# power_supply_board.net
KiCad netlist of a schematic drawn in EAGLE
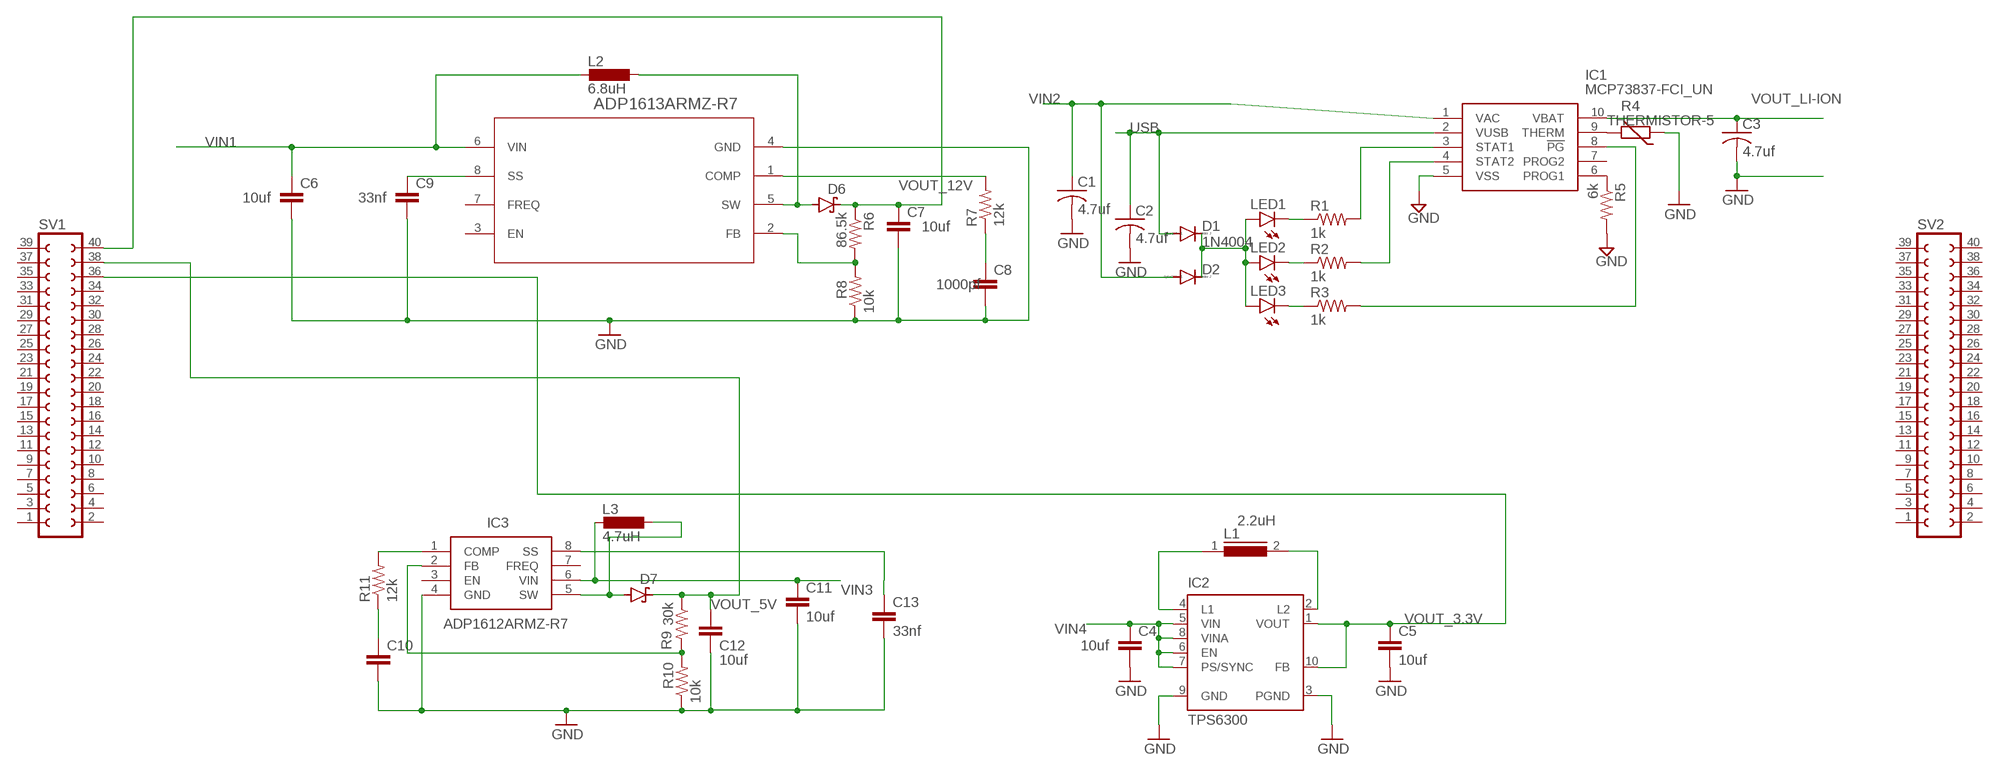
[diagram p0: schematic, sheet 1]

(export (version "E")
  (design (tool "Eeschema 10.0.6"))
  (components
    (comp (ref "C1")
      (value "4.7uf")
      (footprint "eagle-import:C025-024X044")
      (libsource (lib "eagle-import") (part "C-US025-024X044"))
    )
    (comp (ref "C2")
      (value "4.7uf")
      (footprint "eagle-import:C025-024X044")
      (libsource (lib "eagle-import") (part "C-US025-024X044"))
    )
    (comp (ref "C3")
      (value "4.7uf")
      (footprint "eagle-import:C025-024X044")
      (libsource (lib "eagle-import") (part "C-US025-024X044"))
    )
    (comp (ref "C4")
      (value "10uf")
      (footprint "eagle-import:C2.5-3")
      (libsource (lib "eagle-import") (part "C2,5-3"))
    )
    (comp (ref "C5")
      (value "10uf")
      (footprint "eagle-import:C2.5-3")
      (libsource (lib "eagle-import") (part "C2,5-3"))
    )
    (comp (ref "C6")
      (value "10uf")
      (footprint "eagle-import:C2.5-3")
      (libsource (lib "eagle-import") (part "C2,5-3"))
    )
    (comp (ref "C7")
      (value "10uf")
      (footprint "eagle-import:C2.5-3")
      (libsource (lib "eagle-import") (part "C2,5-3"))
    )
    (comp (ref "C8")
      (value "1000pf")
      (footprint "eagle-import:C2.5-3")
      (libsource (lib "eagle-import") (part "C2,5-3"))
    )
    (comp (ref "C9")
      (value "33nf")
      (footprint "eagle-import:C2.5-3")
      (libsource (lib "eagle-import") (part "C2,5-3"))
    )
    (comp (ref "C10")
      (value "1200pf")
      (footprint "eagle-import:C2.5-3")
      (libsource (lib "eagle-import") (part "C2,5-3"))
    )
    (comp (ref "C11")
      (value "10uf")
      (footprint "eagle-import:C2.5-3")
      (libsource (lib "eagle-import") (part "C2,5-3"))
    )
    (comp (ref "C12")
      (value "10uf")
      (footprint "eagle-import:C2.5-3")
      (libsource (lib "eagle-import") (part "C2,5-3"))
    )
    (comp (ref "C13")
      (value "33nf")
      (footprint "eagle-import:C2.5-3")
      (libsource (lib "eagle-import") (part "C2,5-3"))
    )
    (comp (ref "D1")
      (value "1N4004")
      (footprint "eagle-import:DO41-10")
      (libsource (lib "eagle-import") (part "1N4004"))
    )
    (comp (ref "D2")
      (value "1N4004")
      (footprint "eagle-import:DO41-10")
      (libsource (lib "eagle-import") (part "1N4004"))
    )
    (comp (ref "D6")
      (value "3A,40V")
      (footprint "eagle-import:SMC")
      (libsource (lib "eagle-import") (part "MBRS30T32"))
    )
    (comp (ref "D7")
      (value "3A,40V")
      (footprint "eagle-import:SMC")
      (libsource (lib "eagle-import") (part "MBRS30T32"))
    )
    (comp (ref "IC1")
      (value "MCP73837-FCI_UN")
      (footprint "eagle-import:SOP50P490X110-10N")
      (fields
        (field (name "ARROW_PART_NUMBER") "MCP73837-FCI/UN")
        (field (name "MOUSER_PART_NUMBER") "579-MCP73837-FCI/UN")
      )
      (libsource (lib "eagle-import") (part "MCP73837-FCI_UN"))
    )
    (comp (ref "IC2")
      (value "TPS6300")
      (footprint "eagle-import:DRC-S-PVSON-N10")
      (fields (field (name "MPN") "TPS63000DRCTG4"))
      (libsource (lib "eagle-import") (part "TPS6300"))
    )
    (comp (ref "IC3")
      (value "ADP1612ARMZ-R7")
      (footprint "eagle-import:SOP65P490X110-8N")
      (fields (field (name "MOUSER_PART_NUMBER") "584-ADP1612ARMZ-R7"))
      (libsource (lib "eagle-import") (part "ADP1612ARMZ-R7"))
    )
    (comp (ref "L1")
      (value "2.2uH")
      (footprint "eagle-import:SLF7045")
      (libsource (lib "eagle-import") (part "SLF7045"))
    )
    (comp (ref "L2")
      (value "6.8uH")
      (footprint "eagle-import:DO3316P")
      (libsource (lib "eagle-import") (part "DO3316P"))
    )
    (comp (ref "L3")
      (value "4.7uH")
      (footprint "eagle-import:DO3316P")
      (libsource (lib "eagle-import") (part "DO3316P"))
    )
    (comp (ref "LED1")
      (value "LAP4-BOTTOM")
      (footprint "eagle-import:P47F-BOTTOM")
      (libsource (lib "eagle-import") (part "P4-BOTTOMLA"))
    )
    (comp (ref "LED2")
      (value "LAP4-BOTTOM")
      (footprint "eagle-import:P47F-BOTTOM")
      (libsource (lib "eagle-import") (part "P4-BOTTOMLA"))
    )
    (comp (ref "LED3")
      (value "LAP4-BOTTOM")
      (footprint "eagle-import:P47F-BOTTOM")
      (libsource (lib "eagle-import") (part "P4-BOTTOMLA"))
    )
    (comp (ref "R1")
      (value "1k")
      (footprint "eagle-import:0204V")
      (libsource (lib "eagle-import") (part "R-US_0204/2V"))
    )
    (comp (ref "R2")
      (value "1k")
      (footprint "eagle-import:0204V")
      (libsource (lib "eagle-import") (part "R-US_0204/2V"))
    )
    (comp (ref "R3")
      (value "1k")
      (footprint "eagle-import:0204V")
      (libsource (lib "eagle-import") (part "R-US_0204/2V"))
    )
    (comp (ref "R4")
      (value "THERMISTOR-5")
      (footprint "eagle-import:R-5")
      (libsource (lib "eagle-import") (part "THERMISTOR-5"))
    )
    (comp (ref "R5")
      (value "6k")
      (footprint "eagle-import:0204V")
      (libsource (lib "eagle-import") (part "R-US_0204/2V"))
    )
    (comp (ref "R6")
      (value "86.5k")
      (footprint "eagle-import:M0805")
      (libsource (lib "eagle-import") (part "R-US_M0805"))
    )
    (comp (ref "R7")
      (value "12k")
      (footprint "eagle-import:M0805")
      (libsource (lib "eagle-import") (part "R-US_M0805"))
    )
    (comp (ref "R8")
      (value "10k")
      (footprint "eagle-import:M0805")
      (libsource (lib "eagle-import") (part "R-US_M0805"))
    )
    (comp (ref "R9")
      (value "30k")
      (footprint "eagle-import:M0805")
      (libsource (lib "eagle-import") (part "R-US_M0805"))
    )
    (comp (ref "R10")
      (value "10k")
      (footprint "eagle-import:M0805")
      (libsource (lib "eagle-import") (part "R-US_M0805"))
    )
    (comp (ref "R11")
      (value "12k")
      (footprint "eagle-import:M0805")
      (libsource (lib "eagle-import") (part "R-US_M0805"))
    )
    (comp (ref "SV1")
      (value "FE20-2")
      (footprint "eagle-import:FE20-2")
      (libsource (lib "eagle-import") (part "FE20-2"))
    )
    (comp (ref "SV2")
      (value "FE20-2")
      (footprint "eagle-import:FE20-2")
      (libsource (lib "eagle-import") (part "FE20-2"))
    )
    (comp (ref "U1")
      (value "ADP1613ARMZ-R7")
      (footprint "eagle-import:RM_8_ADI")
      (libsource (lib "eagle-import") (part "ADP1613ARMZ-R7"))
    )
  )
  (nets
    (net (code "1") (name "/USB") (class "Default")
      (node (ref "C2") (pin "1") (pinfunction "1_1") (pintype "passive"))
      (node (ref "D1") (pin "A") (pinfunction "A_A") (pintype "passive"))
      (node (ref "IC1") (pin "2") (pinfunction "VUSB_2") (pintype "bidirectional"))
    )
    (net (code "2") (name "/VIN1") (class "Default")
      (node (ref "C6") (pin "1") (pinfunction "1_1") (pintype "passive"))
      (node (ref "L2") (pin "1") (pinfunction "1_1") (pintype "passive"))
      (node (ref "U1") (pin "6") (pinfunction "VIN_6") (pintype "passive"))
    )
    (net (code "3") (name "/VIN2") (class "Default")
      (node (ref "C1") (pin "1") (pinfunction "1_1") (pintype "passive"))
      (node (ref "D2") (pin "A") (pinfunction "A_A") (pintype "passive"))
      (node (ref "IC1") (pin "1") (pinfunction "VAC_1") (pintype "bidirectional"))
    )
    (net (code "4") (name "/VIN3") (class "Default")
      (node (ref "C11") (pin "1") (pinfunction "1_1") (pintype "passive"))
      (node (ref "IC3") (pin "6") (pinfunction "VIN_6") (pintype "bidirectional"))
      (node (ref "L3") (pin "1") (pinfunction "1_1") (pintype "passive"))
    )
    (net (code "5") (name "/VIN4") (class "Default")
      (node (ref "C4") (pin "1") (pinfunction "1_1") (pintype "passive"))
      (node (ref "IC2") (pin "5") (pinfunction "VIN_5") (pintype "input"))
      (node (ref "IC2") (pin "6") (pinfunction "EN_6") (pintype "input"))
      (node (ref "IC2") (pin "7") (pinfunction "PS/SYNC_7") (pintype "input"))
      (node (ref "IC2") (pin "8") (pinfunction "VINA_8") (pintype "input"))
    )
    (net (code "6") (name "/VOUT_3.3V") (class "Default")
      (node (ref "C5") (pin "1") (pinfunction "1_1") (pintype "passive"))
      (node (ref "IC2") (pin "1") (pinfunction "VOUT_1") (pintype "output"))
      (node (ref "IC2") (pin "10") (pinfunction "FB_10") (pintype "input"))
      (node (ref "SV1") (pin "36") (pinfunction "36_36") (pintype "passive"))
    )
    (net (code "7") (name "/VOUT_5V") (class "Default")
      (node (ref "C12") (pin "1") (pinfunction "1_1") (pintype "passive"))
      (node (ref "D7") (pin "C") (pinfunction "C_C") (pintype "passive"))
      (node (ref "R9") (pin "1") (pinfunction "1_1") (pintype "passive"))
      (node (ref "SV1") (pin "38") (pinfunction "38_38") (pintype "passive"))
    )
    (net (code "8") (name "/VOUT_12V") (class "Default")
      (node (ref "C7") (pin "1") (pinfunction "1_1") (pintype "passive"))
      (node (ref "D6") (pin "C") (pinfunction "C_C") (pintype "passive"))
      (node (ref "R6") (pin "1") (pinfunction "1_1") (pintype "passive"))
      (node (ref "SV1") (pin "40") (pinfunction "40_40") (pintype "passive"))
    )
    (net (code "9") (name "/VOUT_LI-ION") (class "Default")
      (node (ref "C3") (pin "1") (pinfunction "1_1") (pintype "passive"))
      (node (ref "IC1") (pin "10") (pinfunction "VBAT_10") (pintype "bidirectional"))
    )
    (net (code "10") (name "GND") (class "Default")
      (node (ref "C1") (pin "2") (pinfunction "2_2") (pintype "passive"))
      (node (ref "C10") (pin "2") (pinfunction "2_2") (pintype "passive"))
      (node (ref "C11") (pin "2") (pinfunction "2_2") (pintype "passive"))
      (node (ref "C12") (pin "2") (pinfunction "2_2") (pintype "passive"))
      (node (ref "C13") (pin "2") (pinfunction "2_2") (pintype "passive"))
      (node (ref "C2") (pin "2") (pinfunction "2_2") (pintype "passive"))
      (node (ref "C3") (pin "2") (pinfunction "2_2") (pintype "passive"))
      (node (ref "C4") (pin "2") (pinfunction "2_2") (pintype "passive"))
      (node (ref "C5") (pin "2") (pinfunction "2_2") (pintype "passive"))
      (node (ref "C6") (pin "2") (pinfunction "2_2") (pintype "passive"))
      (node (ref "C7") (pin "2") (pinfunction "2_2") (pintype "passive"))
      (node (ref "C8") (pin "2") (pinfunction "2_2") (pintype "passive"))
      (node (ref "C9") (pin "2") (pinfunction "2_2") (pintype "passive"))
      (node (ref "IC1") (pin "5") (pinfunction "VSS_5") (pintype "power_in"))
      (node (ref "IC2") (pin "3") (pinfunction "PGND_3") (pintype "power_in"))
      (node (ref "IC2") (pin "9") (pinfunction "GND_9") (pintype "power_in"))
      (node (ref "IC3") (pin "4") (pinfunction "GND_4") (pintype "bidirectional"))
      (node (ref "R10") (pin "1") (pinfunction "1_1") (pintype "passive"))
      (node (ref "R4") (pin "1") (pinfunction "1_1") (pintype "passive"))
      (node (ref "R5") (pin "2") (pinfunction "2_2") (pintype "passive"))
      (node (ref "R8") (pin "1") (pinfunction "1_1") (pintype "passive"))
      (node (ref "U1") (pin "4") (pinfunction "GND_4") (pintype "passive"))
    )
    (net (code "11") (name "Net-(C8-Pad1)") (class "Default")
      (node (ref "C8") (pin "1") (pinfunction "1_1") (pintype "passive"))
      (node (ref "R7") (pin "1") (pinfunction "1_1") (pintype "passive"))
    )
    (net (code "12") (name "Net-(C10-Pad1)") (class "Default")
      (node (ref "C10") (pin "1") (pinfunction "1_1") (pintype "passive"))
      (node (ref "R11") (pin "1") (pinfunction "1_1") (pintype "passive"))
    )
    (net (code "13") (name "Net-(D1-PadC)") (class "Default")
      (node (ref "D1") (pin "C") (pinfunction "C_C") (pintype "passive"))
      (node (ref "D2") (pin "C") (pinfunction "C_C") (pintype "passive"))
      (node (ref "LED1") (pin "A") (pinfunction "A_A") (pintype "passive"))
      (node (ref "LED2") (pin "A") (pinfunction "A_A") (pintype "passive"))
      (node (ref "LED3") (pin "A") (pinfunction "A_A") (pintype "passive"))
    )
    (net (code "14") (name "Net-(IC1-PROG1)") (class "Default")
      (node (ref "IC1") (pin "6") (pinfunction "PROG1_6") (pintype "bidirectional"))
      (node (ref "R5") (pin "1") (pinfunction "1_1") (pintype "passive"))
    )
    (net (code "15") (name "Net-(IC1-STAT1)") (class "Default")
      (node (ref "IC1") (pin "3") (pinfunction "STAT1_3") (pintype "bidirectional"))
      (node (ref "R1") (pin "2") (pinfunction "2_2") (pintype "passive"))
    )
    (net (code "16") (name "Net-(IC1-STAT2)") (class "Default")
      (node (ref "IC1") (pin "4") (pinfunction "STAT2_4") (pintype "bidirectional"))
      (node (ref "R2") (pin "2") (pinfunction "2_2") (pintype "passive"))
    )
    (net (code "17") (name "Net-(IC1-THERM)") (class "Default")
      (node (ref "IC1") (pin "9") (pinfunction "THERM_9") (pintype "bidirectional"))
      (node (ref "R4") (pin "2") (pinfunction "2_2") (pintype "passive"))
    )
    (net (code "18") (name "Net-(IC1-~{PG})") (class "Default")
      (node (ref "IC1") (pin "8") (pinfunction "~{PG}_8") (pintype "bidirectional"))
      (node (ref "R3") (pin "2") (pinfunction "2_2") (pintype "passive"))
    )
    (net (code "19") (name "Net-(IC2A-L1)") (class "Default")
      (node (ref "IC2") (pin "4") (pinfunction "L1_4") (pintype "passive"))
      (node (ref "L1") (pin "1") (pinfunction "1_1") (pintype "passive"))
    )
    (net (code "20") (name "Net-(IC2A-L2)") (class "Default")
      (node (ref "IC2") (pin "2") (pinfunction "L2_2") (pintype "passive"))
      (node (ref "L1") (pin "2") (pinfunction "2_2") (pintype "passive"))
    )
    (net (code "21") (name "Net-(IC3-COMP)") (class "Default")
      (node (ref "IC3") (pin "1") (pinfunction "COMP_1") (pintype "bidirectional"))
      (node (ref "R11") (pin "2") (pinfunction "2_2") (pintype "passive"))
    )
    (net (code "22") (name "Net-(IC3-FB)") (class "Default")
      (node (ref "IC3") (pin "2") (pinfunction "FB_2") (pintype "bidirectional"))
      (node (ref "R10") (pin "2") (pinfunction "2_2") (pintype "passive"))
      (node (ref "R9") (pin "2") (pinfunction "2_2") (pintype "passive"))
    )
    (net (code "23") (name "Net-(IC3-SS)") (class "Default")
      (node (ref "C13") (pin "1") (pinfunction "1_1") (pintype "passive"))
      (node (ref "IC3") (pin "8") (pinfunction "SS_8") (pintype "bidirectional"))
    )
    (net (code "24") (name "Net-(IC3-SW)") (class "Default")
      (node (ref "D7") (pin "A") (pinfunction "A_A") (pintype "passive"))
      (node (ref "IC3") (pin "5") (pinfunction "SW_5") (pintype "bidirectional"))
      (node (ref "L3") (pin "2") (pinfunction "2_2") (pintype "passive"))
    )
    (net (code "25") (name "Net-(LED1-PadC)") (class "Default")
      (node (ref "LED1") (pin "C") (pinfunction "C_C") (pintype "passive"))
      (node (ref "R1") (pin "1") (pinfunction "1_1") (pintype "passive"))
    )
    (net (code "26") (name "Net-(LED2-PadC)") (class "Default")
      (node (ref "LED2") (pin "C") (pinfunction "C_C") (pintype "passive"))
      (node (ref "R2") (pin "1") (pinfunction "1_1") (pintype "passive"))
    )
    (net (code "27") (name "Net-(LED3-PadC)") (class "Default")
      (node (ref "LED3") (pin "C") (pinfunction "C_C") (pintype "passive"))
      (node (ref "R3") (pin "1") (pinfunction "1_1") (pintype "passive"))
    )
    (net (code "28") (name "Net-(U1-COMP)") (class "Default")
      (node (ref "R7") (pin "2") (pinfunction "2_2") (pintype "passive"))
      (node (ref "U1") (pin "1") (pinfunction "COMP_1") (pintype "passive"))
    )
    (net (code "29") (name "Net-(U1-FB)") (class "Default")
      (node (ref "R6") (pin "2") (pinfunction "2_2") (pintype "passive"))
      (node (ref "R8") (pin "2") (pinfunction "2_2") (pintype "passive"))
      (node (ref "U1") (pin "2") (pinfunction "FB_2") (pintype "passive"))
    )
    (net (code "30") (name "Net-(U1-SS)") (class "Default")
      (node (ref "C9") (pin "1") (pinfunction "1_1") (pintype "passive"))
      (node (ref "U1") (pin "8") (pinfunction "SS_8") (pintype "passive"))
    )
    (net (code "31") (name "Net-(U1-SW)") (class "Default")
      (node (ref "D6") (pin "A") (pinfunction "A_A") (pintype "passive"))
      (node (ref "L2") (pin "2") (pinfunction "2_2") (pintype "passive"))
      (node (ref "U1") (pin "5") (pinfunction "SW_5") (pintype "passive"))
    )
    (net (code "32") (name "unconnected-(IC1-PROG2-Pad7)") (class "Default")
      (node (ref "IC1") (pin "7") (pinfunction "PROG2_7") (pintype "bidirectional"))
    )
    (net (code "33") (name "unconnected-(IC3-EN-Pad3)") (class "Default")
      (node (ref "IC3") (pin "3") (pinfunction "EN_3") (pintype "bidirectional"))
    )
    (net (code "34") (name "unconnected-(IC3-FREQ-Pad7)") (class "Default")
      (node (ref "IC3") (pin "7") (pinfunction "FREQ_7") (pintype "bidirectional"))
    )
    (net (code "35") (name "unconnected-(SV1-Pad1)") (class "Default")
      (node (ref "SV1") (pin "1") (pinfunction "1_1") (pintype "passive"))
    )
    (net (code "36") (name "unconnected-(SV1-Pad2)") (class "Default")
      (node (ref "SV1") (pin "2") (pinfunction "2_2") (pintype "passive"))
    )
    (net (code "37") (name "unconnected-(SV1-Pad3)") (class "Default")
      (node (ref "SV1") (pin "3") (pinfunction "3_3") (pintype "passive"))
    )
    (net (code "38") (name "unconnected-(SV1-Pad4)") (class "Default")
      (node (ref "SV1") (pin "4") (pinfunction "4_4") (pintype "passive"))
    )
    (net (code "39") (name "unconnected-(SV1-Pad5)") (class "Default")
      (node (ref "SV1") (pin "5") (pinfunction "5_5") (pintype "passive"))
    )
    (net (code "40") (name "unconnected-(SV1-Pad6)") (class "Default")
      (node (ref "SV1") (pin "6") (pinfunction "6_6") (pintype "passive"))
    )
    (net (code "41") (name "unconnected-(SV1-Pad7)") (class "Default")
      (node (ref "SV1") (pin "7") (pinfunction "7_7") (pintype "passive"))
    )
    (net (code "42") (name "unconnected-(SV1-Pad8)") (class "Default")
      (node (ref "SV1") (pin "8") (pinfunction "8_8") (pintype "passive"))
    )
    (net (code "43") (name "unconnected-(SV1-Pad9)") (class "Default")
      (node (ref "SV1") (pin "9") (pinfunction "9_9") (pintype "passive"))
    )
    (net (code "44") (name "unconnected-(SV1-Pad10)") (class "Default")
      (node (ref "SV1") (pin "10") (pinfunction "10_10") (pintype "passive"))
    )
    (net (code "45") (name "unconnected-(SV1-Pad11)") (class "Default")
      (node (ref "SV1") (pin "11") (pinfunction "11_11") (pintype "passive"))
    )
    (net (code "46") (name "unconnected-(SV1-Pad12)") (class "Default")
      (node (ref "SV1") (pin "12") (pinfunction "12_12") (pintype "passive"))
    )
    (net (code "47") (name "unconnected-(SV1-Pad13)") (class "Default")
      (node (ref "SV1") (pin "13") (pinfunction "13_13") (pintype "passive"))
    )
    (net (code "48") (name "unconnected-(SV1-Pad14)") (class "Default")
      (node (ref "SV1") (pin "14") (pinfunction "14_14") (pintype "passive"))
    )
    (net (code "49") (name "unconnected-(SV1-Pad15)") (class "Default")
      (node (ref "SV1") (pin "15") (pinfunction "15_15") (pintype "passive"))
    )
    (net (code "50") (name "unconnected-(SV1-Pad16)") (class "Default")
      (node (ref "SV1") (pin "16") (pinfunction "16_16") (pintype "passive"))
    )
    (net (code "51") (name "unconnected-(SV1-Pad17)") (class "Default")
      (node (ref "SV1") (pin "17") (pinfunction "17_17") (pintype "passive"))
    )
    (net (code "52") (name "unconnected-(SV1-Pad18)") (class "Default")
      (node (ref "SV1") (pin "18") (pinfunction "18_18") (pintype "passive"))
    )
    (net (code "53") (name "unconnected-(SV1-Pad19)") (class "Default")
      (node (ref "SV1") (pin "19") (pinfunction "19_19") (pintype "passive"))
    )
    (net (code "54") (name "unconnected-(SV1-Pad20)") (class "Default")
      (node (ref "SV1") (pin "20") (pinfunction "20_20") (pintype "passive"))
    )
    (net (code "55") (name "unconnected-(SV1-Pad21)") (class "Default")
      (node (ref "SV1") (pin "21") (pinfunction "21_21") (pintype "passive"))
    )
    (net (code "56") (name "unconnected-(SV1-Pad22)") (class "Default")
      (node (ref "SV1") (pin "22") (pinfunction "22_22") (pintype "passive"))
    )
    (net (code "57") (name "unconnected-(SV1-Pad23)") (class "Default")
      (node (ref "SV1") (pin "23") (pinfunction "23_23") (pintype "passive"))
    )
    (net (code "58") (name "unconnected-(SV1-Pad24)") (class "Default")
      (node (ref "SV1") (pin "24") (pinfunction "24_24") (pintype "passive"))
    )
    (net (code "59") (name "unconnected-(SV1-Pad25)") (class "Default")
      (node (ref "SV1") (pin "25") (pinfunction "25_25") (pintype "passive"))
    )
    (net (code "60") (name "unconnected-(SV1-Pad26)") (class "Default")
      (node (ref "SV1") (pin "26") (pinfunction "26_26") (pintype "passive"))
    )
    (net (code "61") (name "unconnected-(SV1-Pad27)") (class "Default")
      (node (ref "SV1") (pin "27") (pinfunction "27_27") (pintype "passive"))
    )
    (net (code "62") (name "unconnected-(SV1-Pad28)") (class "Default")
      (node (ref "SV1") (pin "28") (pinfunction "28_28") (pintype "passive"))
    )
    (net (code "63") (name "unconnected-(SV1-Pad29)") (class "Default")
      (node (ref "SV1") (pin "29") (pinfunction "29_29") (pintype "passive"))
    )
    (net (code "64") (name "unconnected-(SV1-Pad30)") (class "Default")
      (node (ref "SV1") (pin "30") (pinfunction "30_30") (pintype "passive"))
    )
    (net (code "65") (name "unconnected-(SV1-Pad31)") (class "Default")
      (node (ref "SV1") (pin "31") (pinfunction "31_31") (pintype "passive"))
    )
    (net (code "66") (name "unconnected-(SV1-Pad32)") (class "Default")
      (node (ref "SV1") (pin "32") (pinfunction "32_32") (pintype "passive"))
    )
    (net (code "67") (name "unconnected-(SV1-Pad33)") (class "Default")
      (node (ref "SV1") (pin "33") (pinfunction "33_33") (pintype "passive"))
    )
    (net (code "68") (name "unconnected-(SV1-Pad34)") (class "Default")
      (node (ref "SV1") (pin "34") (pinfunction "34_34") (pintype "passive"))
    )
    (net (code "69") (name "unconnected-(SV1-Pad35)") (class "Default")
      (node (ref "SV1") (pin "35") (pinfunction "35_35") (pintype "passive"))
    )
    (net (code "70") (name "unconnected-(SV1-Pad37)") (class "Default")
      (node (ref "SV1") (pin "37") (pinfunction "37_37") (pintype "passive"))
    )
    (net (code "71") (name "unconnected-(SV1-Pad39)") (class "Default")
      (node (ref "SV1") (pin "39") (pinfunction "39_39") (pintype "passive"))
    )
    (net (code "72") (name "unconnected-(SV2-Pad1)") (class "Default")
      (node (ref "SV2") (pin "1") (pinfunction "1_1") (pintype "passive"))
    )
    (net (code "73") (name "unconnected-(SV2-Pad2)") (class "Default")
      (node (ref "SV2") (pin "2") (pinfunction "2_2") (pintype "passive"))
    )
    (net (code "74") (name "unconnected-(SV2-Pad3)") (class "Default")
      (node (ref "SV2") (pin "3") (pinfunction "3_3") (pintype "passive"))
    )
    (net (code "75") (name "unconnected-(SV2-Pad4)") (class "Default")
      (node (ref "SV2") (pin "4") (pinfunction "4_4") (pintype "passive"))
    )
    (net (code "76") (name "unconnected-(SV2-Pad5)") (class "Default")
      (node (ref "SV2") (pin "5") (pinfunction "5_5") (pintype "passive"))
    )
    (net (code "77") (name "unconnected-(SV2-Pad6)") (class "Default")
      (node (ref "SV2") (pin "6") (pinfunction "6_6") (pintype "passive"))
    )
    (net (code "78") (name "unconnected-(SV2-Pad7)") (class "Default")
      (node (ref "SV2") (pin "7") (pinfunction "7_7") (pintype "passive"))
    )
    (net (code "79") (name "unconnected-(SV2-Pad8)") (class "Default")
      (node (ref "SV2") (pin "8") (pinfunction "8_8") (pintype "passive"))
    )
    (net (code "80") (name "unconnected-(SV2-Pad9)") (class "Default")
      (node (ref "SV2") (pin "9") (pinfunction "9_9") (pintype "passive"))
    )
    (net (code "81") (name "unconnected-(SV2-Pad10)") (class "Default")
      (node (ref "SV2") (pin "10") (pinfunction "10_10") (pintype "passive"))
    )
    (net (code "82") (name "unconnected-(SV2-Pad11)") (class "Default")
      (node (ref "SV2") (pin "11") (pinfunction "11_11") (pintype "passive"))
    )
    (net (code "83") (name "unconnected-(SV2-Pad12)") (class "Default")
      (node (ref "SV2") (pin "12") (pinfunction "12_12") (pintype "passive"))
    )
    (net (code "84") (name "unconnected-(SV2-Pad13)") (class "Default")
      (node (ref "SV2") (pin "13") (pinfunction "13_13") (pintype "passive"))
    )
    (net (code "85") (name "unconnected-(SV2-Pad14)") (class "Default")
      (node (ref "SV2") (pin "14") (pinfunction "14_14") (pintype "passive"))
    )
    (net (code "86") (name "unconnected-(SV2-Pad15)") (class "Default")
      (node (ref "SV2") (pin "15") (pinfunction "15_15") (pintype "passive"))
    )
    (net (code "87") (name "unconnected-(SV2-Pad16)") (class "Default")
      (node (ref "SV2") (pin "16") (pinfunction "16_16") (pintype "passive"))
    )
    (net (code "88") (name "unconnected-(SV2-Pad17)") (class "Default")
      (node (ref "SV2") (pin "17") (pinfunction "17_17") (pintype "passive"))
    )
    (net (code "89") (name "unconnected-(SV2-Pad18)") (class "Default")
      (node (ref "SV2") (pin "18") (pinfunction "18_18") (pintype "passive"))
    )
    (net (code "90") (name "unconnected-(SV2-Pad19)") (class "Default")
      (node (ref "SV2") (pin "19") (pinfunction "19_19") (pintype "passive"))
    )
    (net (code "91") (name "unconnected-(SV2-Pad20)") (class "Default")
      (node (ref "SV2") (pin "20") (pinfunction "20_20") (pintype "passive"))
    )
    (net (code "92") (name "unconnected-(SV2-Pad21)") (class "Default")
      (node (ref "SV2") (pin "21") (pinfunction "21_21") (pintype "passive"))
    )
    (net (code "93") (name "unconnected-(SV2-Pad22)") (class "Default")
      (node (ref "SV2") (pin "22") (pinfunction "22_22") (pintype "passive"))
    )
    (net (code "94") (name "unconnected-(SV2-Pad23)") (class "Default")
      (node (ref "SV2") (pin "23") (pinfunction "23_23") (pintype "passive"))
    )
    (net (code "95") (name "unconnected-(SV2-Pad24)") (class "Default")
      (node (ref "SV2") (pin "24") (pinfunction "24_24") (pintype "passive"))
    )
    (net (code "96") (name "unconnected-(SV2-Pad25)") (class "Default")
      (node (ref "SV2") (pin "25") (pinfunction "25_25") (pintype "passive"))
    )
    (net (code "97") (name "unconnected-(SV2-Pad26)") (class "Default")
      (node (ref "SV2") (pin "26") (pinfunction "26_26") (pintype "passive"))
    )
    (net (code "98") (name "unconnected-(SV2-Pad27)") (class "Default")
      (node (ref "SV2") (pin "27") (pinfunction "27_27") (pintype "passive"))
    )
    (net (code "99") (name "unconnected-(SV2-Pad28)") (class "Default")
      (node (ref "SV2") (pin "28") (pinfunction "28_28") (pintype "passive"))
    )
    (net (code "100") (name "unconnected-(SV2-Pad29)") (class "Default")
      (node (ref "SV2") (pin "29") (pinfunction "29_29") (pintype "passive"))
    )
    (net (code "101") (name "unconnected-(SV2-Pad30)") (class "Default")
      (node (ref "SV2") (pin "30") (pinfunction "30_30") (pintype "passive"))
    )
    (net (code "102") (name "unconnected-(SV2-Pad31)") (class "Default")
      (node (ref "SV2") (pin "31") (pinfunction "31_31") (pintype "passive"))
    )
    (net (code "103") (name "unconnected-(SV2-Pad32)") (class "Default")
      (node (ref "SV2") (pin "32") (pinfunction "32_32") (pintype "passive"))
    )
    (net (code "104") (name "unconnected-(SV2-Pad33)") (class "Default")
      (node (ref "SV2") (pin "33") (pinfunction "33_33") (pintype "passive"))
    )
    (net (code "105") (name "unconnected-(SV2-Pad34)") (class "Default")
      (node (ref "SV2") (pin "34") (pinfunction "34_34") (pintype "passive"))
    )
    (net (code "106") (name "unconnected-(SV2-Pad35)") (class "Default")
      (node (ref "SV2") (pin "35") (pinfunction "35_35") (pintype "passive"))
    )
    (net (code "107") (name "unconnected-(SV2-Pad36)") (class "Default")
      (node (ref "SV2") (pin "36") (pinfunction "36_36") (pintype "passive"))
    )
    (net (code "108") (name "unconnected-(SV2-Pad37)") (class "Default")
      (node (ref "SV2") (pin "37") (pinfunction "37_37") (pintype "passive"))
    )
    (net (code "109") (name "unconnected-(SV2-Pad38)") (class "Default")
      (node (ref "SV2") (pin "38") (pinfunction "38_38") (pintype "passive"))
    )
    (net (code "110") (name "unconnected-(SV2-Pad39)") (class "Default")
      (node (ref "SV2") (pin "39") (pinfunction "39_39") (pintype "passive"))
    )
    (net (code "111") (name "unconnected-(SV2-Pad40)") (class "Default")
      (node (ref "SV2") (pin "40") (pinfunction "40_40") (pintype "passive"))
    )
    (net (code "112") (name "unconnected-(U1-EN-Pad3)") (class "Default")
      (node (ref "U1") (pin "3") (pinfunction "EN_3") (pintype "passive"))
    )
    (net (code "113") (name "unconnected-(U1-FREQ-Pad7)") (class "Default")
      (node (ref "U1") (pin "7") (pinfunction "FREQ_7") (pintype "passive"))
    )
  )
)
